# PowerSupply.net
KiCad netlist of a schematic drawn in Altium Designer
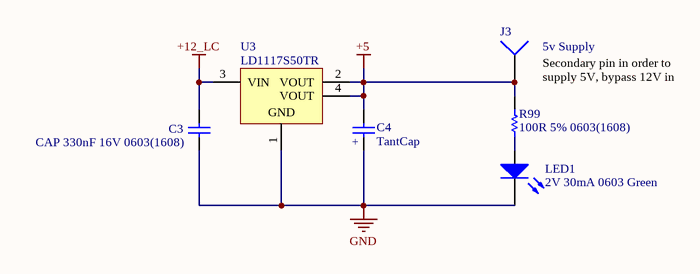
[diagram p0: PowerSupply.SchDoc]

(export (version "E")
  (design (tool "Eeschema 10.0.6"))
  (components
    (comp (ref "C3")
      (value "CAP 330nF 16V 0603(1608)")
      (footprint "CAPC0603(1608)100_M")
      (description "CAP 330nF 16V ±5% 0603 (1608 Metric) Thickness 1mm SMD")
      (fields (field (name "TOLERANCE") "Â±5%"))
      (libsource (lib "Altium Content Vault") (part "CAP"))
    )
    (comp (ref "C4")
      (value "TantCap")
      (footprint "TantCap_2917 (7343)")
      (libsource (lib "RPI GPIO BOARD") (part "TantCap"))
    )
    (comp (ref "J3")
      (value "5v Supply")
      (footprint "PIN1")
      (description "Socket")
      (fields (field (name "PUBLISHER") "Altium Limited"))
      (libsource (lib "Miscellaneous Connectors") (part "Socket"))
    )
    (comp (ref "LED1")
      (value "2V 30mA 0603 Green")
      (footprint "0603_A")
      (description "SMD mono-color Chip LED, WL-SMCW, Bright Green")
      (fields (field (name "PARTNUMBER") "150060VS75000") (field (name "MANUFACTURER") "Wuerth Elektronik"))
      (libsource (lib "Altium Content Vault") (part "WE-LED_K1A2-2"))
    )
    (comp (ref "R99")
      (value "100R 5% 0603(1608)")
      (footprint "RESC0603(1608)_L")
      (description "100R 0.1W 5% 0603 (1608 Metric)  SMD")
      (fields (field (name "TOLERANCE") "5 %") (field (name "POWER") "0.1 W"))
      (libsource (lib "Altium Content Vault") (part "RES"))
    )
    (comp (ref "U3")
      (value "LD1117S50TR")
      (footprint "SOT-223_L")
      (description "Fixed Low Drop Positive Voltage Regulator, 5V, 4-Pin SOT-223, Tape and Reel")
      (libsource (lib "Altium Content Vault") (part "PM-REG-LD1117-SOT4"))
    )
  )
  (nets
    (net (code "1") (name "+5") (class "Default")
      (node (ref "C4") (pin "2") (pinfunction "2_2") (pintype "passive"))
      (node (ref "J3") (pin "1") (pinfunction "1_1") (pintype "passive"))
      (node (ref "R99") (pin "1") (pinfunction "1_1") (pintype "passive"))
      (node (ref "U3") (pin "2") (pinfunction "VOUT_2") (pintype "power_in"))
      (node (ref "U3") (pin "4") (pinfunction "VOUT_4") (pintype "power_in"))
    )
    (net (code "2") (name "+12_LC") (class "Default")
      (node (ref "C3") (pin "2") (pinfunction "2_2") (pintype "passive"))
      (node (ref "U3") (pin "3") (pinfunction "VIN_3") (pintype "power_in"))
    )
    (net (code "3") (name "GND") (class "Default")
      (node (ref "C3") (pin "1") (pinfunction "1_1") (pintype "passive"))
      (node (ref "C4") (pin "1") (pinfunction "1_1") (pintype "passive"))
      (node (ref "LED1") (pin "1") (pinfunction "K_1") (pintype "passive"))
      (node (ref "U3") (pin "1") (pinfunction "GND_1") (pintype "power_in"))
    )
    (net (code "4") (name "Net-(LED1-A)") (class "Default")
      (node (ref "LED1") (pin "2") (pinfunction "A_2") (pintype "passive"))
      (node (ref "R99") (pin "2") (pinfunction "2_2") (pintype "passive"))
    )
  )
)
